# LoRaDevBreakout_FW_RevA.net
KiCad netlist of a schematic drawn in EAGLE
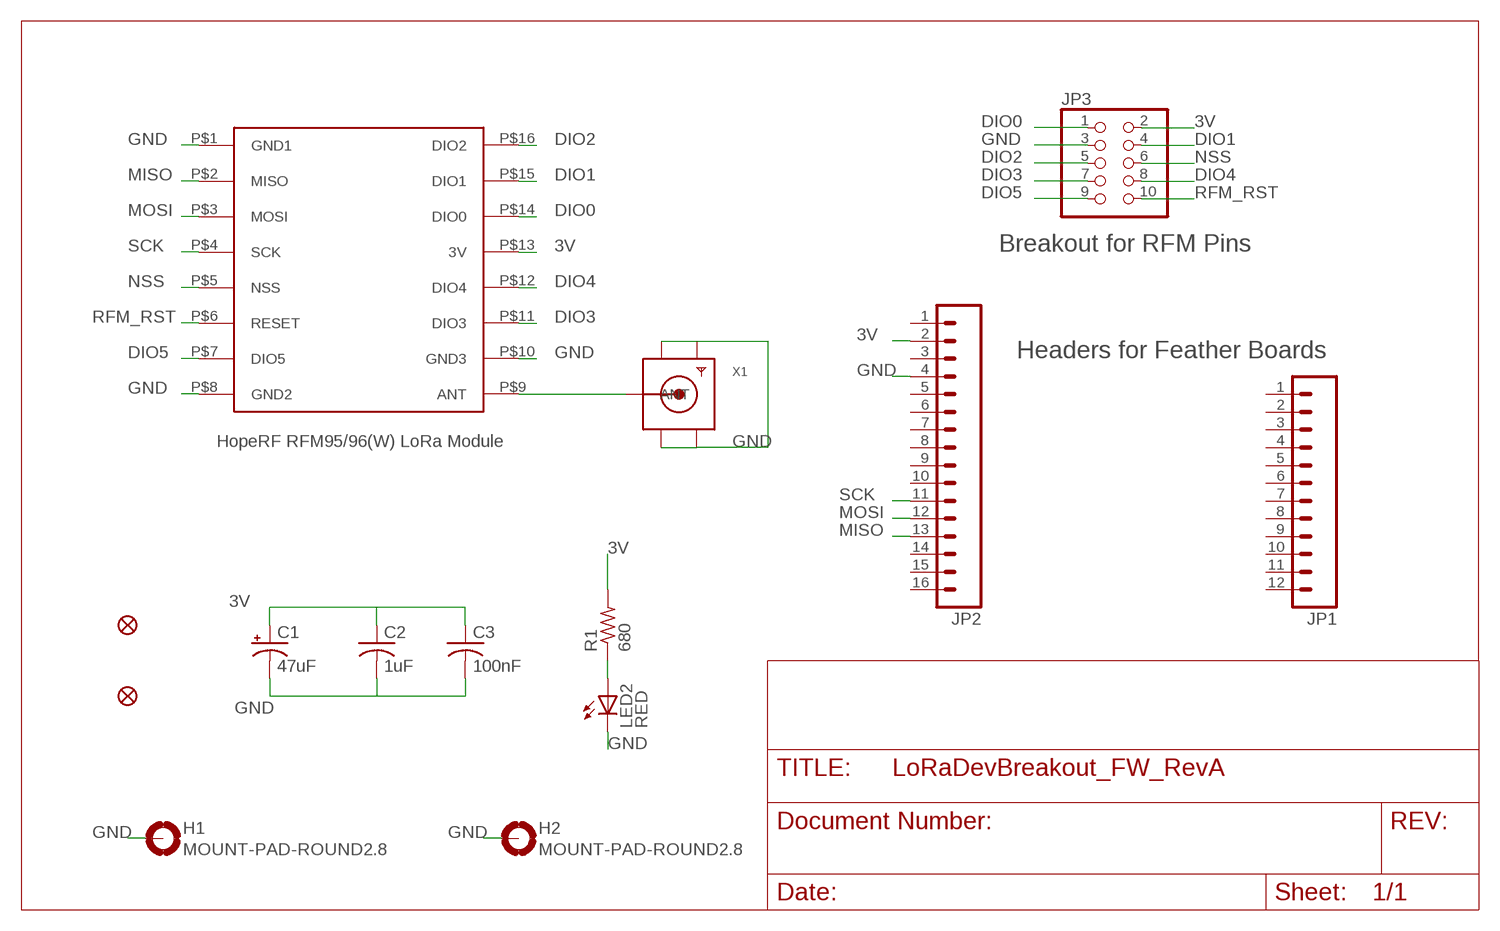
[diagram p0: schematic, sheet 1]

(export (version "E")
  (design (tool "Eeschema 10.0.6"))
  (components
    (comp (ref "C1")
      (value "47uF")
      (footprint "eagle-import:EIA3528")
      (libsource (lib "eagle-import") (part "47UF-10V-10%(TANT)"))
    )
    (comp (ref "C2")
      (value "1uF")
      (footprint "eagle-import:C0603")
      (libsource (lib "eagle-import") (part "C-USC0603"))
    )
    (comp (ref "C3")
      (value "100nF")
      (footprint "eagle-import:C0603")
      (libsource (lib "eagle-import") (part "C-USC0603"))
    )
    (comp (ref "FID1")
      (value "FIDUCIAL1X2")
      (footprint "eagle-import:FIDUCIAL-1X2")
      (libsource (lib "eagle-import") (part "FIDUCIAL1X2"))
    )
    (comp (ref "FID2")
      (value "FIDUCIAL1X2")
      (footprint "eagle-import:FIDUCIAL-1X2")
      (libsource (lib "eagle-import") (part "FIDUCIAL1X2"))
    )
    (comp (ref "H1")
      (value "MOUNT-PAD-ROUND2.8")
      (footprint "eagle-import:2,8-PAD")
      (libsource (lib "eagle-import") (part "MOUNT-PAD-ROUND2.8"))
    )
    (comp (ref "H2")
      (value "MOUNT-PAD-ROUND2.8")
      (footprint "eagle-import:2,8-PAD")
      (libsource (lib "eagle-import") (part "MOUNT-PAD-ROUND2.8"))
    )
    (comp (ref "JP1")
      (value "M12NO_SILK")
      (footprint "eagle-import:1X12_NO_SILK")
      (libsource (lib "eagle-import") (part "M12NO_SILK"))
    )
    (comp (ref "JP2")
      (value "M161X16_NO_SILK")
      (footprint "eagle-import:1X16_NO_SILK")
      (libsource (lib "eagle-import") (part "M161X16_NO_SILK"))
    )
    (comp (ref "JP3")
      (value "PINHD-2X5")
      (footprint "eagle-import:2X05")
      (libsource (lib "eagle-import") (part "PINHD-2X5"))
    )
    (comp (ref "LED2")
      (value "RED")
      (footprint "eagle-import:CHIPLED_0805")
      (libsource (lib "eagle-import") (part "LEDCHIPLED_0805"))
    )
    (comp (ref "R1")
      (value "680")
      (footprint "eagle-import:R0603")
      (libsource (lib "eagle-import") (part "R-US_R0603"))
    )
    (comp (ref "U$2")
      (value "RFM95W")
      (footprint "eagle-import:RFM95W")
      (libsource (lib "eagle-import") (part "RFM95W"))
    )
    (comp (ref "X1")
      (value "SMACONNECTOR_EDGE")
      (footprint "eagle-import:SMA_EDGELAUNCH")
      (libsource (lib "eagle-import") (part "SMACONNECTOR_EDGE"))
    )
  )
  (nets
    (net (code "1") (name "/3V") (class "Default")
      (node (ref "C1") (pin "A") (pinfunction "+_A") (pintype "passive"))
      (node (ref "C2") (pin "1") (pinfunction "1_1") (pintype "passive"))
      (node (ref "C3") (pin "1") (pinfunction "1_1") (pintype "passive"))
      (node (ref "JP2") (pin "2") (pinfunction "2_2") (pintype "passive"))
      (node (ref "JP3") (pin "2") (pinfunction "2_2") (pintype "passive"))
      (node (ref "R1") (pin "2") (pinfunction "2_2") (pintype "passive"))
      (node (ref "U$2") (pin "P$13") (pinfunction "3V_P$13") (pintype "bidirectional"))
    )
    (net (code "2") (name "/DIO0") (class "Default")
      (node (ref "JP3") (pin "1") (pinfunction "1_1") (pintype "passive"))
      (node (ref "U$2") (pin "P$14") (pinfunction "DIO0_P$14") (pintype "bidirectional"))
    )
    (net (code "3") (name "/DIO1") (class "Default")
      (node (ref "JP3") (pin "4") (pinfunction "4_4") (pintype "passive"))
      (node (ref "U$2") (pin "P$15") (pinfunction "DIO1_P$15") (pintype "bidirectional"))
    )
    (net (code "4") (name "/DIO2") (class "Default")
      (node (ref "JP3") (pin "5") (pinfunction "5_5") (pintype "passive"))
      (node (ref "U$2") (pin "P$16") (pinfunction "DIO2_P$16") (pintype "bidirectional"))
    )
    (net (code "5") (name "/DIO3") (class "Default")
      (node (ref "JP3") (pin "7") (pinfunction "7_7") (pintype "passive"))
      (node (ref "U$2") (pin "P$11") (pinfunction "DIO3_P$11") (pintype "bidirectional"))
    )
    (net (code "6") (name "/DIO4") (class "Default")
      (node (ref "JP3") (pin "8") (pinfunction "8_8") (pintype "passive"))
      (node (ref "U$2") (pin "P$12") (pinfunction "DIO4_P$12") (pintype "bidirectional"))
    )
    (net (code "7") (name "/DIO5") (class "Default")
      (node (ref "JP3") (pin "9") (pinfunction "9_9") (pintype "passive"))
      (node (ref "U$2") (pin "P$7") (pinfunction "DIO5_P$7") (pintype "bidirectional"))
    )
    (net (code "8") (name "/GND") (class "Default")
      (node (ref "C1") (pin "C") (pinfunction "-_C") (pintype "passive"))
      (node (ref "C2") (pin "2") (pinfunction "2_2") (pintype "passive"))
      (node (ref "C3") (pin "2") (pinfunction "2_2") (pintype "passive"))
      (node (ref "H1") (pin "B2,8") (pinfunction "MOUNT_B2,8") (pintype "passive"))
      (node (ref "H2") (pin "B2,8") (pinfunction "MOUNT_B2,8") (pintype "passive"))
      (node (ref "JP2") (pin "4") (pinfunction "4_4") (pintype "passive"))
      (node (ref "JP3") (pin "3") (pinfunction "3_3") (pintype "passive"))
      (node (ref "LED2") (pin "C") (pinfunction "C_C") (pintype "passive"))
      (node (ref "U$2") (pin "P$1") (pinfunction "GND1_P$1") (pintype "bidirectional"))
      (node (ref "U$2") (pin "P$10") (pinfunction "GND3_P$10") (pintype "bidirectional"))
      (node (ref "U$2") (pin "P$8") (pinfunction "GND2_P$8") (pintype "bidirectional"))
      (node (ref "X1") (pin "GND@1") (pinfunction "GND4_GND@1") (pintype "power_in"))
      (node (ref "X1") (pin "GND@2") (pinfunction "GND3_GND@2") (pintype "power_in"))
      (node (ref "X1") (pin "GND@3") (pinfunction "GND2_GND@3") (pintype "power_in"))
      (node (ref "X1") (pin "GND@4") (pinfunction "GND1_GND@4") (pintype "power_in"))
    )
    (net (code "9") (name "/MISO") (class "Default")
      (node (ref "JP2") (pin "13") (pinfunction "13_13") (pintype "passive"))
      (node (ref "U$2") (pin "P$2") (pinfunction "MISO_P$2") (pintype "bidirectional"))
    )
    (net (code "10") (name "/MOSI") (class "Default")
      (node (ref "JP2") (pin "12") (pinfunction "12_12") (pintype "passive"))
      (node (ref "U$2") (pin "P$3") (pinfunction "MOSI_P$3") (pintype "bidirectional"))
    )
    (net (code "11") (name "/NSS") (class "Default")
      (node (ref "JP3") (pin "6") (pinfunction "6_6") (pintype "passive"))
      (node (ref "U$2") (pin "P$5") (pinfunction "NSS_P$5") (pintype "bidirectional"))
    )
    (net (code "12") (name "/RFM_RST") (class "Default")
      (node (ref "JP3") (pin "10") (pinfunction "10_10") (pintype "passive"))
      (node (ref "U$2") (pin "P$6") (pinfunction "RESET_P$6") (pintype "bidirectional"))
    )
    (net (code "13") (name "/SCK") (class "Default")
      (node (ref "JP2") (pin "11") (pinfunction "11_11") (pintype "passive"))
      (node (ref "U$2") (pin "P$4") (pinfunction "SCK_P$4") (pintype "bidirectional"))
    )
    (net (code "14") (name "Net-(LED2-PadA)") (class "Default")
      (node (ref "LED2") (pin "A") (pinfunction "A_A") (pintype "passive"))
      (node (ref "R1") (pin "1") (pinfunction "1_1") (pintype "passive"))
    )
    (net (code "15") (name "Net-(U$2-ANT)") (class "Default")
      (node (ref "U$2") (pin "P$9") (pinfunction "ANT_P$9") (pintype "bidirectional"))
      (node (ref "X1") (pin "P") (pinfunction "ANT_P") (pintype "bidirectional"))
    )
    (net (code "16") (name "unconnected-(JP1-Pad1)") (class "Default")
      (node (ref "JP1") (pin "1") (pinfunction "1_1") (pintype "passive"))
    )
    (net (code "17") (name "unconnected-(JP1-Pad2)") (class "Default")
      (node (ref "JP1") (pin "2") (pinfunction "2_2") (pintype "passive"))
    )
    (net (code "18") (name "unconnected-(JP1-Pad3)") (class "Default")
      (node (ref "JP1") (pin "3") (pinfunction "3_3") (pintype "passive"))
    )
    (net (code "19") (name "unconnected-(JP1-Pad4)") (class "Default")
      (node (ref "JP1") (pin "4") (pinfunction "4_4") (pintype "passive"))
    )
    (net (code "20") (name "unconnected-(JP1-Pad5)") (class "Default")
      (node (ref "JP1") (pin "5") (pinfunction "5_5") (pintype "passive"))
    )
    (net (code "21") (name "unconnected-(JP1-Pad6)") (class "Default")
      (node (ref "JP1") (pin "6") (pinfunction "6_6") (pintype "passive"))
    )
    (net (code "22") (name "unconnected-(JP1-Pad7)") (class "Default")
      (node (ref "JP1") (pin "7") (pinfunction "7_7") (pintype "passive"))
    )
    (net (code "23") (name "unconnected-(JP1-Pad8)") (class "Default")
      (node (ref "JP1") (pin "8") (pinfunction "8_8") (pintype "passive"))
    )
    (net (code "24") (name "unconnected-(JP1-Pad9)") (class "Default")
      (node (ref "JP1") (pin "9") (pinfunction "9_9") (pintype "passive"))
    )
    (net (code "25") (name "unconnected-(JP1-Pad10)") (class "Default")
      (node (ref "JP1") (pin "10") (pinfunction "10_10") (pintype "passive"))
    )
    (net (code "26") (name "unconnected-(JP1-Pad11)") (class "Default")
      (node (ref "JP1") (pin "11") (pinfunction "11_11") (pintype "passive"))
    )
    (net (code "27") (name "unconnected-(JP1-Pad12)") (class "Default")
      (node (ref "JP1") (pin "12") (pinfunction "12_12") (pintype "passive"))
    )
    (net (code "28") (name "unconnected-(JP2-Pad1)") (class "Default")
      (node (ref "JP2") (pin "1") (pinfunction "1_1") (pintype "passive"))
    )
    (net (code "29") (name "unconnected-(JP2-Pad3)") (class "Default")
      (node (ref "JP2") (pin "3") (pinfunction "3_3") (pintype "passive"))
    )
    (net (code "30") (name "unconnected-(JP2-Pad5)") (class "Default")
      (node (ref "JP2") (pin "5") (pinfunction "5_5") (pintype "passive"))
    )
    (net (code "31") (name "unconnected-(JP2-Pad6)") (class "Default")
      (node (ref "JP2") (pin "6") (pinfunction "6_6") (pintype "passive"))
    )
    (net (code "32") (name "unconnected-(JP2-Pad7)") (class "Default")
      (node (ref "JP2") (pin "7") (pinfunction "7_7") (pintype "passive"))
    )
    (net (code "33") (name "unconnected-(JP2-Pad8)") (class "Default")
      (node (ref "JP2") (pin "8") (pinfunction "8_8") (pintype "passive"))
    )
    (net (code "34") (name "unconnected-(JP2-Pad9)") (class "Default")
      (node (ref "JP2") (pin "9") (pinfunction "9_9") (pintype "passive"))
    )
    (net (code "35") (name "unconnected-(JP2-Pad10)") (class "Default")
      (node (ref "JP2") (pin "10") (pinfunction "10_10") (pintype "passive"))
    )
    (net (code "36") (name "unconnected-(JP2-Pad14)") (class "Default")
      (node (ref "JP2") (pin "14") (pinfunction "14_14") (pintype "passive"))
    )
    (net (code "37") (name "unconnected-(JP2-Pad15)") (class "Default")
      (node (ref "JP2") (pin "15") (pinfunction "15_15") (pintype "passive"))
    )
    (net (code "38") (name "unconnected-(JP2-Pad16)") (class "Default")
      (node (ref "JP2") (pin "16") (pinfunction "16_16") (pintype "passive"))
    )
  )
)
